# BSU_Power.net
KiCad netlist of a schematic drawn in Altium Designer
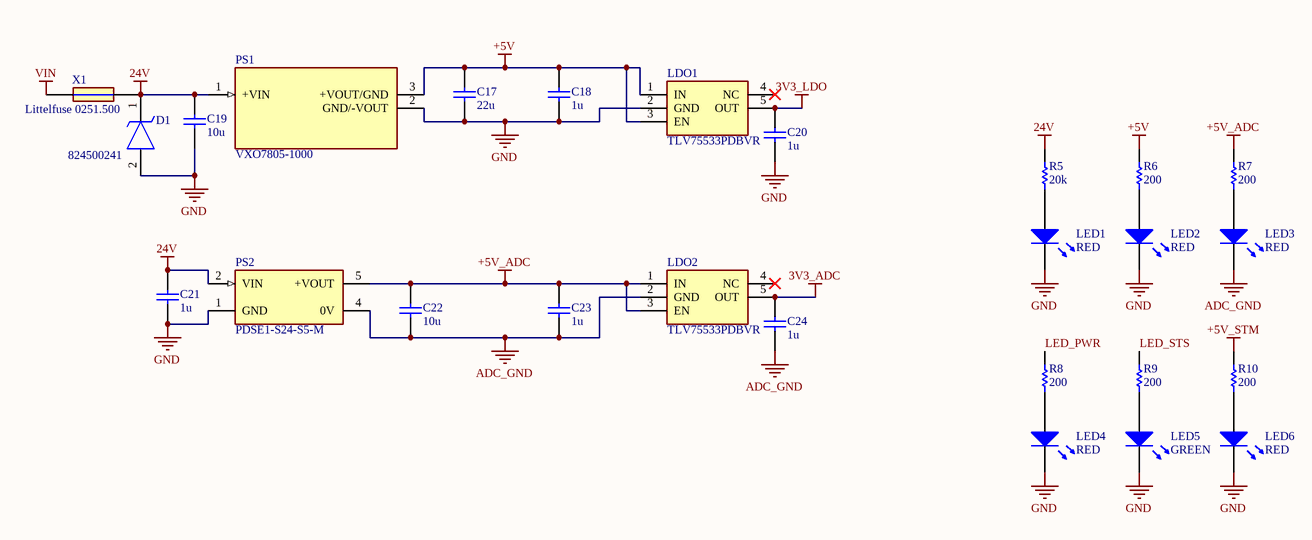
[diagram p0: BSU_Power.SchDoc]

(export (version "E")
  (design (tool "Eeschema 10.0.6"))
  (components
    (comp (ref "C17")
      (value "22u")
      (footprint "0805_SMD_C")
      (description "0805 SMD Capacitor")
      (libsource (lib "BMS_ShareComponentLibrary") (part "0805_SMD_Capacitor"))
    )
    (comp (ref "C18")
      (value "1u")
      (footprint "0805_SMD_C")
      (description "0805 SMD Capacitor")
      (libsource (lib "BMS_ShareComponentLibrary") (part "0805_SMD_Capacitor"))
    )
    (comp (ref "C19")
      (value "10u")
      (footprint "0805_SMD_C")
      (description "0805 SMD Capacitor")
      (libsource (lib "BMS_ShareComponentLibrary") (part "0805_SMD_Capacitor"))
    )
    (comp (ref "C20")
      (value "1u")
      (footprint "0805_SMD_C")
      (description "0805 SMD Capacitor")
      (libsource (lib "BMS_ShareComponentLibrary") (part "0805_SMD_Capacitor"))
    )
    (comp (ref "C21")
      (value "1u")
      (footprint "0805_SMD_C")
      (description "0805 SMD Capacitor")
      (libsource (lib "BMS_ShareComponentLibrary") (part "0805_SMD_Capacitor"))
    )
    (comp (ref "C22")
      (value "10u")
      (footprint "0805_SMD_C")
      (description "0805 SMD Capacitor")
      (libsource (lib "BMS_ShareComponentLibrary") (part "0805_SMD_Capacitor"))
    )
    (comp (ref "C23")
      (value "1u")
      (footprint "0805_SMD_C")
      (description "0805 SMD Capacitor")
      (libsource (lib "BMS_ShareComponentLibrary") (part "0805_SMD_Capacitor"))
    )
    (comp (ref "C24")
      (value "1u")
      (footprint "0805_SMD_C")
      (description "0805 SMD Capacitor")
      (libsource (lib "BMS_ShareComponentLibrary") (part "0805_SMD_Capacitor"))
    )
    (comp (ref "D1")
      (value "824500241")
      (footprint "SMA_824500241")
      (description "TVS Diode (Uni-directional)")
      (fields (field (name "MOUSER PART NUMBER") "710-824500241"))
      (libsource (lib "BMS_ShareComponentLibrary") (part "824500241"))
    )
    (comp (ref "LDO1")
      (value "TLV75533PDBVR")
      (footprint "SOT23-5_TLV75533")
      (description "LDO Voltage Regulators 500-mA, Low IQ, Small Size, Low Dropout Regulator 5-SOT-23 -40 to 125")
      (fields (field (name "MOUSER PART NUMBER") "595-TLV75533PDBVR"))
      (libsource (lib "BMS_ShareComponentLibrary") (part "3V 500mA LDO"))
    )
    (comp (ref "LDO2")
      (value "TLV75533PDBVR")
      (footprint "SOT23-5_TLV75533")
      (description "LDO Voltage Regulators 500-mA, Low IQ, Small Size, Low Dropout Regulator 5-SOT-23 -40 to 125")
      (fields (field (name "MOUSER PART NUMBER") "595-TLV75533PDBVR"))
      (libsource (lib "BMS_ShareComponentLibrary") (part "3V 500mA LDO"))
    )
    (comp (ref "LED1")
      (value "RED")
      (footprint "0805_SMD_LED")
      (description "SMD LED")
      (libsource (lib "BMS_ShareComponentLibrary") (part "0805 LED Generic"))
    )
    (comp (ref "LED2")
      (value "RED")
      (footprint "0805_SMD_LED")
      (description "SMD LED")
      (libsource (lib "BMS_ShareComponentLibrary") (part "0805 LED Generic"))
    )
    (comp (ref "LED3")
      (value "RED")
      (footprint "0805_SMD_LED")
      (description "SMD LED")
      (libsource (lib "BMS_ShareComponentLibrary") (part "0805 LED Generic"))
    )
    (comp (ref "LED4")
      (value "RED")
      (footprint "0805_SMD_LED")
      (description "SMD LED")
      (libsource (lib "BMS_ShareComponentLibrary") (part "0805 LED Generic"))
    )
    (comp (ref "LED5")
      (value "GREEN")
      (footprint "0805_SMD_LED")
      (description "SMD LED")
      (libsource (lib "BMS_ShareComponentLibrary") (part "0805 LED Generic"))
    )
    (comp (ref "LED6")
      (value "RED")
      (footprint "0805_SMD_LED")
      (description "SMD LED")
      (libsource (lib "BMS_ShareComponentLibrary") (part "0805 LED Generic"))
    )
    (comp (ref "PS1")
      (value "VXO7805-1000")
      (footprint "VXO78xx-1000")
      (description "CUI Inc.,1 A Output Current, 6~36 Vdc Input, 3 Pin SIP, Non-Isolated, Dc-Dc Converter")
      (fields (field (name "MF") "CUI Inc."))
      (libsource (lib "BMS_ShareComponentLibrary") (part "24-5 Power Converter"))
    )
    (comp (ref "PS2")
      (value "PDSE1-S24-S5-M")
      (footprint "PDSE1-Sxx-Sx-M")
      (description "CUI Inc., DC-DC ISOLATED, 5VDC input, 1 W, 4.5-5.5 VDC")
      (fields (field (name "MF") "{'manufacturer': u'CUI'}"))
      (libsource (lib "BMS_ShareComponentLibrary") (part "24-5 Isolated Power Converter"))
    )
    (comp (ref "R5")
      (value "20k")
      (footprint "0805_SMD_R")
      (description "0805 SMD Resistor")
      (libsource (lib "BMS_ShareComponentLibrary") (part "0805_SMD_Resistor"))
    )
    (comp (ref "R6")
      (value "200")
      (footprint "0805_SMD_R")
      (description "0805 SMD Resistor")
      (libsource (lib "BMS_ShareComponentLibrary") (part "0805_SMD_Resistor"))
    )
    (comp (ref "R7")
      (value "200")
      (footprint "0805_SMD_R")
      (description "0805 SMD Resistor")
      (libsource (lib "BMS_ShareComponentLibrary") (part "0805_SMD_Resistor"))
    )
    (comp (ref "R8")
      (value "200")
      (footprint "0805_SMD_R")
      (description "0805 SMD Resistor")
      (libsource (lib "BMS_ShareComponentLibrary") (part "0805_SMD_Resistor"))
    )
    (comp (ref "R9")
      (value "200")
      (footprint "0805_SMD_R")
      (description "0805 SMD Resistor")
      (libsource (lib "BMS_ShareComponentLibrary") (part "0805_SMD_Resistor"))
    )
    (comp (ref "R10")
      (value "200")
      (footprint "0805_SMD_R")
      (description "0805 SMD Resistor")
      (libsource (lib "BMS_ShareComponentLibrary") (part "0805_SMD_Resistor"))
    )
    (comp (ref "X1")
      (value "Littelfuse 0251.500")
      (footprint "LITTELFUSE 0251")
      (description "Littelfuse 251 series 125VAC/125VDC 500mA")
      (libsource (lib "BMS_ShareComponentLibrary") (part "LV Fuse 500mA"))
    )
  )
  (nets
    (net (code "1") (name "+5V") (class "Default")
      (node (ref "C17") (pin "2") (pinfunction "2_2") (pintype "passive"))
      (node (ref "C18") (pin "2") (pinfunction "2_2") (pintype "passive"))
      (node (ref "LDO1") (pin "1") (pinfunction "IN_1") (pintype "passive"))
      (node (ref "LDO1") (pin "3") (pinfunction "EN_3") (pintype "passive"))
      (node (ref "PS1") (pin "3") (pinfunction "+VOUT/GND_3") (pintype "power_in"))
      (node (ref "R6") (pin "2") (pinfunction "2_2") (pintype "passive"))
    )
    (net (code "2") (name "+5V_ADC") (class "Default")
      (node (ref "C22") (pin "2") (pinfunction "2_2") (pintype "passive"))
      (node (ref "C23") (pin "2") (pinfunction "2_2") (pintype "passive"))
      (node (ref "LDO2") (pin "1") (pinfunction "IN_1") (pintype "passive"))
      (node (ref "LDO2") (pin "3") (pinfunction "EN_3") (pintype "passive"))
      (node (ref "PS2") (pin "5") (pinfunction "+VOUT_5") (pintype "power_in"))
      (node (ref "R7") (pin "2") (pinfunction "2_2") (pintype "passive"))
    )
    (net (code "3") (name "+5V_STM") (class "Default")
      (node (ref "R10") (pin "2") (pinfunction "2_2") (pintype "passive"))
    )
    (net (code "4") (name "/LED_PWR") (class "Default")
      (node (ref "R8") (pin "2") (pinfunction "2_2") (pintype "passive"))
    )
    (net (code "5") (name "/LED_STS") (class "Default")
      (node (ref "R9") (pin "2") (pinfunction "2_2") (pintype "passive"))
    )
    (net (code "6") (name "3V3_ADC") (class "Default")
      (node (ref "C24") (pin "2") (pinfunction "2_2") (pintype "passive"))
      (node (ref "LDO2") (pin "5") (pinfunction "OUT_5") (pintype "passive"))
    )
    (net (code "7") (name "3V3_LDO") (class "Default")
      (node (ref "C20") (pin "2") (pinfunction "2_2") (pintype "passive"))
      (node (ref "LDO1") (pin "5") (pinfunction "OUT_5") (pintype "passive"))
    )
    (net (code "8") (name "24V") (class "Default")
      (node (ref "C19") (pin "2") (pinfunction "2_2") (pintype "passive"))
      (node (ref "C21") (pin "2") (pinfunction "2_2") (pintype "passive"))
      (node (ref "D1") (pin "1") (pinfunction "K_1") (pintype "passive"))
      (node (ref "PS1") (pin "1") (pinfunction "+VIN_1") (pintype "input"))
      (node (ref "PS2") (pin "2") (pinfunction "VIN_2") (pintype "input"))
      (node (ref "R5") (pin "2") (pinfunction "2_2") (pintype "passive"))
      (node (ref "X1") (pin "2") (pinfunction "2_2") (pintype "passive"))
    )
    (net (code "9") (name "ADC_GND") (class "Default")
      (node (ref "C22") (pin "1") (pinfunction "1_1") (pintype "passive"))
      (node (ref "C23") (pin "1") (pinfunction "1_1") (pintype "passive"))
      (node (ref "C24") (pin "1") (pinfunction "1_1") (pintype "passive"))
      (node (ref "LDO2") (pin "2") (pinfunction "GND_2") (pintype "passive"))
      (node (ref "LED3") (pin "1") (pinfunction "1_1") (pintype "passive"))
      (node (ref "PS2") (pin "4") (pinfunction "0V_4") (pintype "power_in"))
    )
    (net (code "10") (name "GND") (class "Default")
      (node (ref "C17") (pin "1") (pinfunction "1_1") (pintype "passive"))
      (node (ref "C18") (pin "1") (pinfunction "1_1") (pintype "passive"))
      (node (ref "C19") (pin "1") (pinfunction "1_1") (pintype "passive"))
      (node (ref "C20") (pin "1") (pinfunction "1_1") (pintype "passive"))
      (node (ref "C21") (pin "1") (pinfunction "1_1") (pintype "passive"))
      (node (ref "D1") (pin "2") (pinfunction "A_2") (pintype "passive"))
      (node (ref "LDO1") (pin "2") (pinfunction "GND_2") (pintype "passive"))
      (node (ref "LED1") (pin "1") (pinfunction "1_1") (pintype "passive"))
      (node (ref "LED2") (pin "1") (pinfunction "1_1") (pintype "passive"))
      (node (ref "LED4") (pin "1") (pinfunction "1_1") (pintype "passive"))
      (node (ref "LED5") (pin "1") (pinfunction "1_1") (pintype "passive"))
      (node (ref "LED6") (pin "1") (pinfunction "1_1") (pintype "passive"))
      (node (ref "PS1") (pin "2") (pinfunction "GND/-VOUT_2") (pintype "power_in"))
      (node (ref "PS2") (pin "1") (pinfunction "GND_1") (pintype "power_in"))
    )
    (net (code "11") (name "Net-(LED1-Pad2)") (class "Default")
      (node (ref "LED1") (pin "2") (pinfunction "2_2") (pintype "passive"))
      (node (ref "R5") (pin "1") (pinfunction "1_1") (pintype "passive"))
    )
    (net (code "12") (name "Net-(LED2-Pad2)") (class "Default")
      (node (ref "LED2") (pin "2") (pinfunction "2_2") (pintype "passive"))
      (node (ref "R6") (pin "1") (pinfunction "1_1") (pintype "passive"))
    )
    (net (code "13") (name "Net-(LED3-Pad2)") (class "Default")
      (node (ref "LED3") (pin "2") (pinfunction "2_2") (pintype "passive"))
      (node (ref "R7") (pin "1") (pinfunction "1_1") (pintype "passive"))
    )
    (net (code "14") (name "Net-(LED4-Pad2)") (class "Default")
      (node (ref "LED4") (pin "2") (pinfunction "2_2") (pintype "passive"))
      (node (ref "R8") (pin "1") (pinfunction "1_1") (pintype "passive"))
    )
    (net (code "15") (name "Net-(LED5-Pad2)") (class "Default")
      (node (ref "LED5") (pin "2") (pinfunction "2_2") (pintype "passive"))
      (node (ref "R9") (pin "1") (pinfunction "1_1") (pintype "passive"))
    )
    (net (code "16") (name "Net-(LED6-Pad2)") (class "Default")
      (node (ref "LED6") (pin "2") (pinfunction "2_2") (pintype "passive"))
      (node (ref "R10") (pin "1") (pinfunction "1_1") (pintype "passive"))
    )
    (net (code "17") (name "VIN") (class "Default")
      (node (ref "X1") (pin "1") (pinfunction "1_1") (pintype "passive"))
    )
    (net (code "18") (name "unconnected-(LDO1-NC-Pad4)") (class "Default")
      (node (ref "LDO1") (pin "4") (pinfunction "NC_4") (pintype "passive+no_connect"))
    )
    (net (code "19") (name "unconnected-(LDO2-NC-Pad4)") (class "Default")
      (node (ref "LDO2") (pin "4") (pinfunction "NC_4") (pintype "passive+no_connect"))
    )
  )
)
